# ARC_Shield_0_3.net
KiCad netlist of a schematic drawn in EAGLE
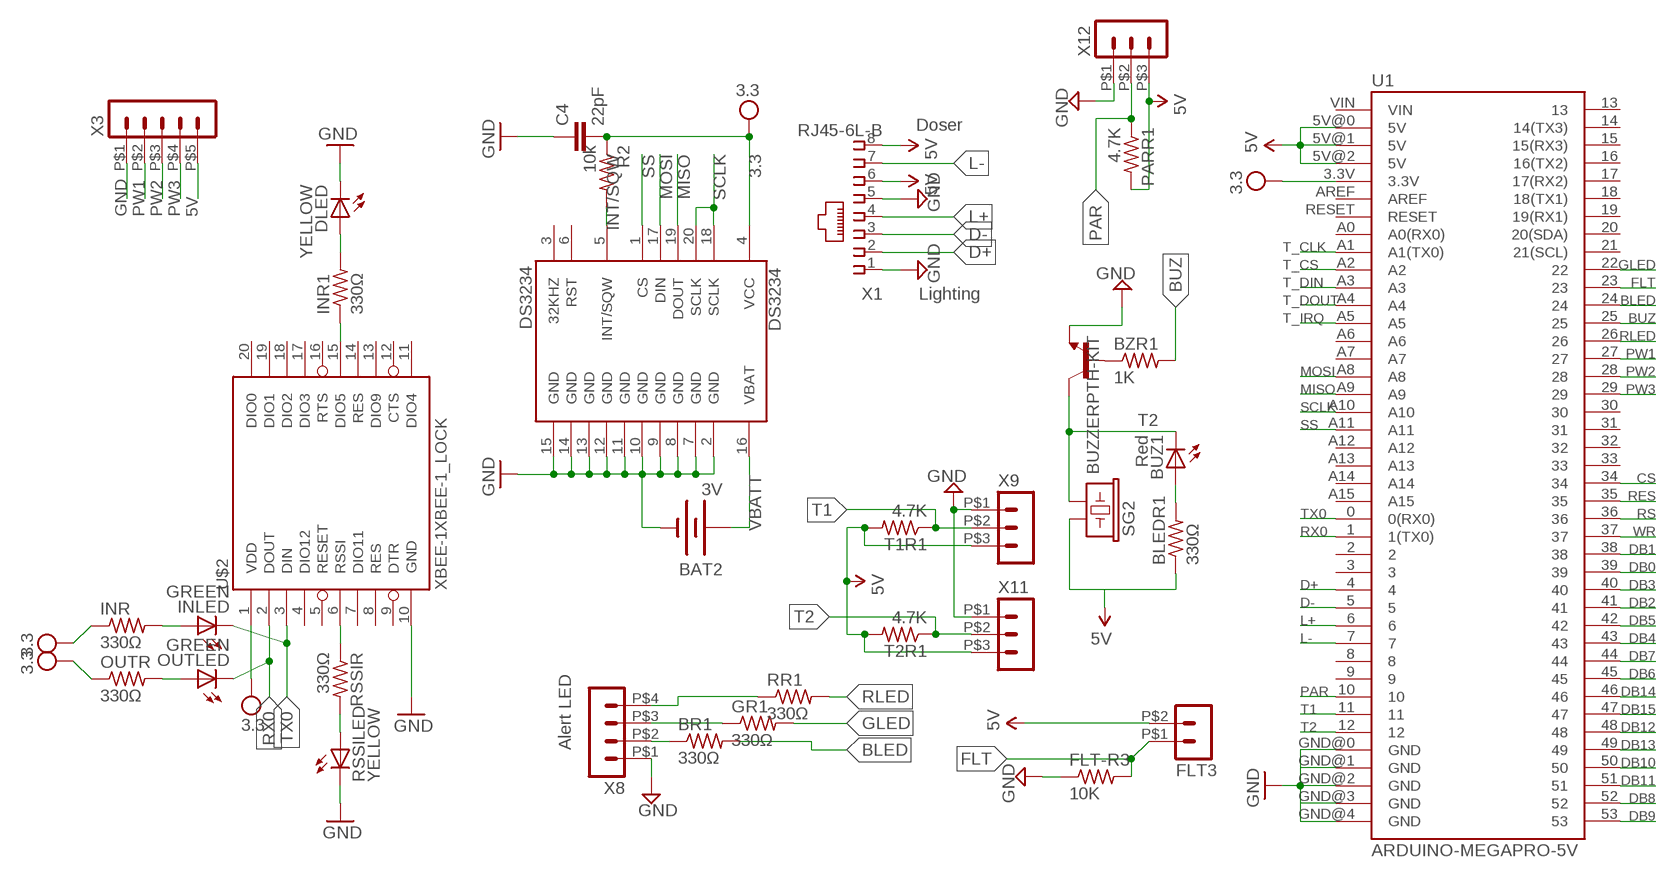
[diagram p0: schematic, sheet 1]

(export (version "E")
  (design (tool "Eeschema 10.0.6"))
  (components
    (comp (ref "BAT2")
      (value "3V")
      (footprint "eagle-import:BATTCON_12MM_CURVED")
      (libsource (lib "eagle-import") (part "BATTERY"))
    )
    (comp (ref "BLEDR1")
      (value "330Ω")
      (footprint "eagle-import:0204_7")
      (libsource (lib "eagle-import") (part "R-US_0204/7"))
    )
    (comp (ref "BR1")
      (value "330Ω")
      (footprint "eagle-import:0204_7")
      (libsource (lib "eagle-import") (part "R-US_0204/7"))
    )
    (comp (ref "BUZ1")
      (value "Red")
      (footprint "eagle-import:LED3MM")
      (libsource (lib "eagle-import") (part "LED3MM"))
    )
    (comp (ref "BZR1")
      (value "1K")
      (footprint "eagle-import:0204_7")
      (libsource (lib "eagle-import") (part "R-US_0204/7"))
    )
    (comp (ref "C4")
      (value "22pF")
      (footprint "eagle-import:C5B3")
      (libsource (lib "eagle-import") (part "C5/3"))
    )
    (comp (ref "DLED")
      (value "YELLOW")
      (footprint "eagle-import:LED3MM")
      (libsource (lib "eagle-import") (part "LED3MM"))
    )
    (comp (ref "DS3234")
      (value "DS3234")
      (footprint "eagle-import:DS3234")
      (libsource (lib "eagle-import") (part "DS3234"))
    )
    (comp (ref "FLT-R3")
      (value "10K")
      (footprint "eagle-import:0204_7")
      (libsource (lib "eagle-import") (part "R-US_0204/7"))
    )
    (comp (ref "FLT3")
      (value "HEADER_POS2_43045-0200")
      (footprint "eagle-import:43045-0200")
      (libsource (lib "eagle-import") (part "HEADER_POS2_?43045-0200"))
    )
    (comp (ref "GR1")
      (value "330Ω")
      (footprint "eagle-import:0204_7")
      (libsource (lib "eagle-import") (part "R-US_0204/7"))
    )
    (comp (ref "INLED")
      (value "GREEN")
      (footprint "eagle-import:LED3MM")
      (libsource (lib "eagle-import") (part "LED3MM"))
    )
    (comp (ref "INR")
      (value "330Ω")
      (footprint "eagle-import:0204_7")
      (libsource (lib "eagle-import") (part "R-US_0204/7"))
    )
    (comp (ref "INR1")
      (value "330Ω")
      (footprint "eagle-import:0204_7")
      (libsource (lib "eagle-import") (part "R-US_0204/7"))
    )
    (comp (ref "OUTLED")
      (value "GREEN")
      (footprint "eagle-import:LED3MM")
      (libsource (lib "eagle-import") (part "LED3MM"))
    )
    (comp (ref "OUTR")
      (value "330Ω")
      (footprint "eagle-import:0204_7")
      (libsource (lib "eagle-import") (part "R-US_0204/7"))
    )
    (comp (ref "PARR1")
      (value "4.7K")
      (footprint "eagle-import:0204_7")
      (libsource (lib "eagle-import") (part "R-US_0204/7"))
    )
    (comp (ref "R2")
      (value "10k")
      (footprint "eagle-import:0204_7")
      (libsource (lib "eagle-import") (part "R-US_0204/7"))
    )
    (comp (ref "RR1")
      (value "330Ω")
      (footprint "eagle-import:0204_7")
      (libsource (lib "eagle-import") (part "R-US_0204/7"))
    )
    (comp (ref "RSSILED")
      (value "YELLOW")
      (footprint "eagle-import:LED3MM")
      (libsource (lib "eagle-import") (part "LED3MM"))
    )
    (comp (ref "RSSIR")
      (value "330Ω")
      (footprint "eagle-import:0204_7")
      (libsource (lib "eagle-import") (part "R-US_0204/7"))
    )
    (comp (ref "SG2")
      (value "BUZZERPTH-KIT")
      (footprint "eagle-import:BUZZER-12MM-KIT")
      (libsource (lib "eagle-import") (part "BUZZERPTH-KIT"))
    )
    (comp (ref "T1R1")
      (value "4.7K")
      (footprint "eagle-import:0204_7")
      (libsource (lib "eagle-import") (part "R-US_0204/7"))
    )
    (comp (ref "T2")
      (value "-NPN-TO92")
      (footprint "eagle-import:TO92")
      (libsource (lib "eagle-import") (part "-NPN-TO92"))
    )
    (comp (ref "T2R1")
      (value "4.7K")
      (footprint "eagle-import:0204_7")
      (libsource (lib "eagle-import") (part "R-US_0204/7"))
    )
    (comp (ref "U$2")
      (value "XBEE-1XBEE-1_LOCK")
      (footprint "eagle-import:XBEE-1_LOCK")
      (libsource (lib "eagle-import") (part "XBEE-1XBEE-1_LOCK"))
    )
    (comp (ref "U1")
      (value "ARDUINO-MEGAPRO-5V")
      (footprint "eagle-import:ARDUINO_MEGA-PRO-5V")
      (libsource (lib "eagle-import") (part "ARDUINO-MEGAPRO-5V"))
    )
    (comp (ref "X1")
      (value "RJ45-6L-B")
      (footprint "eagle-import:RJ45-NO-SHIELD")
      (libsource (lib "eagle-import") (part "RJ45-6L-B"))
    )
    (comp (ref "X3")
      (value "HEADER_POS5_43650-0500")
      (footprint "eagle-import:43650-0500")
      (libsource (lib "eagle-import") (part "HEADER_POS5_?43650-0500"))
    )
    (comp (ref "X8")
      (value "HEADER_POS4_43045-0401")
      (footprint "eagle-import:43045-0400")
      (libsource (lib "eagle-import") (part "HEADER_POS4_?43045-0401"))
    )
    (comp (ref "X9")
      (value "HEADER_POS3_43650-0300")
      (footprint "eagle-import:43650-0300")
      (libsource (lib "eagle-import") (part "HEADER_POS3_?43650-0300"))
    )
    (comp (ref "X11")
      (value "HEADER_POS3_43650-0300")
      (footprint "eagle-import:43650-0300")
      (libsource (lib "eagle-import") (part "HEADER_POS3_?43650-0300"))
    )
    (comp (ref "X12")
      (value "HEADER_POS3_43650-0300")
      (footprint "eagle-import:43650-0300")
      (libsource (lib "eagle-import") (part "HEADER_POS3_?43650-0300"))
    )
  )
  (nets
    (net (code "1") (name "/CS") (class "Default")
      (node (ref "U1") (pin "34") (pinfunction "34_34") (pintype "bidirectional"))
    )
    (net (code "2") (name "/DB0") (class "Default")
      (node (ref "U1") (pin "39") (pinfunction "39_39") (pintype "bidirectional"))
    )
    (net (code "3") (name "/DB1") (class "Default")
      (node (ref "U1") (pin "38") (pinfunction "38_38") (pintype "bidirectional"))
    )
    (net (code "4") (name "/DB2") (class "Default")
      (node (ref "U1") (pin "41") (pinfunction "41_41") (pintype "bidirectional"))
    )
    (net (code "5") (name "/DB3") (class "Default")
      (node (ref "U1") (pin "40") (pinfunction "40_40") (pintype "bidirectional"))
    )
    (net (code "6") (name "/DB4") (class "Default")
      (node (ref "U1") (pin "43") (pinfunction "43_43") (pintype "bidirectional"))
    )
    (net (code "7") (name "/DB5") (class "Default")
      (node (ref "U1") (pin "42") (pinfunction "42_42") (pintype "bidirectional"))
    )
    (net (code "8") (name "/DB6") (class "Default")
      (node (ref "U1") (pin "45") (pinfunction "45_45") (pintype "bidirectional"))
    )
    (net (code "9") (name "/DB7") (class "Default")
      (node (ref "U1") (pin "44") (pinfunction "44_44") (pintype "bidirectional"))
    )
    (net (code "10") (name "/DB8") (class "Default")
      (node (ref "U1") (pin "52") (pinfunction "52_52") (pintype "bidirectional"))
    )
    (net (code "11") (name "/DB9") (class "Default")
      (node (ref "U1") (pin "53") (pinfunction "53_53") (pintype "bidirectional"))
    )
    (net (code "12") (name "/DB10") (class "Default")
      (node (ref "U1") (pin "50") (pinfunction "50_50") (pintype "bidirectional"))
    )
    (net (code "13") (name "/DB11") (class "Default")
      (node (ref "U1") (pin "51") (pinfunction "51_51") (pintype "bidirectional"))
    )
    (net (code "14") (name "/DB12") (class "Default")
      (node (ref "U1") (pin "48") (pinfunction "48_48") (pintype "bidirectional"))
    )
    (net (code "15") (name "/DB13") (class "Default")
      (node (ref "U1") (pin "49") (pinfunction "49_49") (pintype "bidirectional"))
    )
    (net (code "16") (name "/DB14") (class "Default")
      (node (ref "U1") (pin "46") (pinfunction "46_46") (pintype "bidirectional"))
    )
    (net (code "17") (name "/DB15") (class "Default")
      (node (ref "U1") (pin "47") (pinfunction "47_47") (pintype "bidirectional"))
    )
    (net (code "18") (name "/INT{slash}SQW") (class "Default")
      (node (ref "DS3234") (pin "5") (pinfunction "INT/SQW_5") (pintype "bidirectional"))
      (node (ref "R2") (pin "2") (pinfunction "2_2") (pintype "passive"))
    )
    (net (code "19") (name "/MISO") (class "Default")
      (node (ref "DS3234") (pin "19") (pinfunction "DOUT_19") (pintype "bidirectional"))
      (node (ref "U1") (pin "A9") (pinfunction "A9_A9") (pintype "bidirectional"))
    )
    (net (code "20") (name "/MOSI") (class "Default")
      (node (ref "DS3234") (pin "17") (pinfunction "DIN_17") (pintype "bidirectional"))
      (node (ref "U1") (pin "A8") (pinfunction "A8_A8") (pintype "bidirectional"))
    )
    (net (code "21") (name "/PW1") (class "Default")
      (node (ref "U1") (pin "27") (pinfunction "27_27") (pintype "bidirectional"))
      (node (ref "X3") (pin "P$2") (pinfunction "2_P$2") (pintype "passive"))
    )
    (net (code "22") (name "/PW2") (class "Default")
      (node (ref "U1") (pin "28") (pinfunction "28_28") (pintype "bidirectional"))
      (node (ref "X3") (pin "P$3") (pinfunction "3_P$3") (pintype "passive"))
    )
    (net (code "23") (name "/PW3") (class "Default")
      (node (ref "U1") (pin "29") (pinfunction "29_29") (pintype "bidirectional"))
      (node (ref "X3") (pin "P$4") (pinfunction "4_P$4") (pintype "passive"))
    )
    (net (code "24") (name "/RES") (class "Default")
      (node (ref "U1") (pin "35") (pinfunction "35_35") (pintype "bidirectional"))
    )
    (net (code "25") (name "/RS") (class "Default")
      (node (ref "U1") (pin "36") (pinfunction "36_36") (pintype "bidirectional"))
    )
    (net (code "26") (name "/SCLK") (class "Default")
      (node (ref "DS3234") (pin "18") (pinfunction "SCLK_18") (pintype "bidirectional"))
      (node (ref "DS3234") (pin "20") (pinfunction "SCLK_20") (pintype "bidirectional"))
      (node (ref "U1") (pin "A10") (pinfunction "A10_A10") (pintype "bidirectional"))
    )
    (net (code "27") (name "/SS") (class "Default")
      (node (ref "DS3234") (pin "1") (pinfunction "CS_1") (pintype "bidirectional"))
      (node (ref "U1") (pin "A11") (pinfunction "A11_A11") (pintype "bidirectional"))
    )
    (net (code "28") (name "/T_CLK") (class "Default")
      (node (ref "U1") (pin "A1") (pinfunction "A1(TX0)_A1") (pintype "bidirectional"))
    )
    (net (code "29") (name "/T_CS") (class "Default")
      (node (ref "U1") (pin "A2") (pinfunction "A2_A2") (pintype "bidirectional"))
    )
    (net (code "30") (name "/T_DIN") (class "Default")
      (node (ref "U1") (pin "A3") (pinfunction "A3_A3") (pintype "bidirectional"))
    )
    (net (code "31") (name "/T_DOUT") (class "Default")
      (node (ref "U1") (pin "A4") (pinfunction "A4_A4") (pintype "bidirectional"))
    )
    (net (code "32") (name "/T_IRQ") (class "Default")
      (node (ref "U1") (pin "A5") (pinfunction "A5_A5") (pintype "bidirectional"))
    )
    (net (code "33") (name "/VBATT") (class "Default")
      (node (ref "BAT2") (pin "PWR@1") (pinfunction "+_PWR@1") (pintype "power_in"))
      (node (ref "DS3234") (pin "16") (pinfunction "VBAT_16") (pintype "bidirectional"))
    )
    (net (code "34") (name "/WR") (class "Default")
      (node (ref "U1") (pin "37") (pinfunction "37_37") (pintype "bidirectional"))
    )
    (net (code "35") (name "3.3") (class "Default")
      (node (ref "C4") (pin "2") (pinfunction "2_2") (pintype "passive"))
      (node (ref "DS3234") (pin "4") (pinfunction "VCC_4") (pintype "bidirectional"))
      (node (ref "INR") (pin "1") (pinfunction "1_1") (pintype "passive"))
      (node (ref "OUTR") (pin "1") (pinfunction "1_1") (pintype "passive"))
      (node (ref "R2") (pin "1") (pinfunction "1_1") (pintype "passive"))
      (node (ref "U$2") (pin "1") (pinfunction "VDD_1") (pintype "power_in"))
      (node (ref "U1") (pin "3.3V") (pinfunction "3.3V_3.3V") (pintype "bidirectional"))
    )
    (net (code "36") (name "5V") (class "Default")
      (node (ref "BLEDR1") (pin "1") (pinfunction "1_1") (pintype "passive"))
      (node (ref "FLT3") (pin "P$2") (pinfunction "2_P$2") (pintype "passive"))
      (node (ref "PARR1") (pin "2") (pinfunction "2_2") (pintype "passive"))
      (node (ref "SG2") (pin "+") (pinfunction "1_+") (pintype "passive"))
      (node (ref "T1R1") (pin "2") (pinfunction "2_2") (pintype "passive"))
      (node (ref "T2R1") (pin "2") (pinfunction "2_2") (pintype "passive"))
      (node (ref "U1") (pin "5V@0") (pinfunction "5V_5V@0") (pintype "bidirectional"))
      (node (ref "U1") (pin "5V@1") (pinfunction "5V_5V@1") (pintype "bidirectional"))
      (node (ref "U1") (pin "5V@2") (pinfunction "5V_5V@2") (pintype "bidirectional"))
      (node (ref "X1") (pin "6") (pinfunction "6_6") (pintype "passive"))
      (node (ref "X1") (pin "8") (pinfunction "8_8") (pintype "passive"))
      (node (ref "X11") (pin "P$3") (pinfunction "3_P$3") (pintype "passive"))
      (node (ref "X12") (pin "P$3") (pinfunction "3_P$3") (pintype "passive"))
      (node (ref "X3") (pin "P$5") (pinfunction "5_P$5") (pintype "passive"))
      (node (ref "X9") (pin "P$3") (pinfunction "3_P$3") (pintype "passive"))
    )
    (net (code "37") (name "BLED") (class "Default")
      (node (ref "BR1") (pin "2") (pinfunction "2_2") (pintype "passive"))
      (node (ref "U1") (pin "24") (pinfunction "24_24") (pintype "bidirectional"))
    )
    (net (code "38") (name "BUZ") (class "Default")
      (node (ref "BZR1") (pin "2") (pinfunction "2_2") (pintype "passive"))
      (node (ref "U1") (pin "25") (pinfunction "25_25") (pintype "bidirectional"))
    )
    (net (code "39") (name "D+") (class "Default")
      (node (ref "U1") (pin "4") (pinfunction "4_4") (pintype "bidirectional"))
      (node (ref "X1") (pin "2") (pinfunction "2_2") (pintype "passive"))
    )
    (net (code "40") (name "D-") (class "Default")
      (node (ref "U1") (pin "5") (pinfunction "5_5") (pintype "bidirectional"))
      (node (ref "X1") (pin "3") (pinfunction "3_3") (pintype "passive"))
    )
    (net (code "41") (name "FLT") (class "Default")
      (node (ref "FLT-R3") (pin "2") (pinfunction "2_2") (pintype "passive"))
      (node (ref "FLT3") (pin "P$1") (pinfunction "1_P$1") (pintype "passive"))
      (node (ref "U1") (pin "23") (pinfunction "23_23") (pintype "bidirectional"))
    )
    (net (code "42") (name "GLED") (class "Default")
      (node (ref "GR1") (pin "2") (pinfunction "2_2") (pintype "passive"))
      (node (ref "U1") (pin "22") (pinfunction "22_22") (pintype "bidirectional"))
    )
    (net (code "43") (name "GND") (class "Default")
      (node (ref "BAT2") (pin "GND") (pinfunction "-_GND") (pintype "power_in"))
      (node (ref "C4") (pin "1") (pinfunction "1_1") (pintype "passive"))
      (node (ref "DLED") (pin "K") (pinfunction "C_K") (pintype "passive"))
      (node (ref "DS3234") (pin "10") (pinfunction "GND_10") (pintype "bidirectional"))
      (node (ref "DS3234") (pin "11") (pinfunction "GND_11") (pintype "bidirectional"))
      (node (ref "DS3234") (pin "12") (pinfunction "GND_12") (pintype "bidirectional"))
      (node (ref "DS3234") (pin "13") (pinfunction "GND_13") (pintype "bidirectional"))
      (node (ref "DS3234") (pin "14") (pinfunction "GND_14") (pintype "bidirectional"))
      (node (ref "DS3234") (pin "15") (pinfunction "GND_15") (pintype "bidirectional"))
      (node (ref "DS3234") (pin "2") (pinfunction "GND_2") (pintype "bidirectional"))
      (node (ref "DS3234") (pin "7") (pinfunction "GND_7") (pintype "bidirectional"))
      (node (ref "DS3234") (pin "8") (pinfunction "GND_8") (pintype "bidirectional"))
      (node (ref "DS3234") (pin "9") (pinfunction "GND_9") (pintype "bidirectional"))
      (node (ref "FLT-R3") (pin "1") (pinfunction "1_1") (pintype "passive"))
      (node (ref "RSSILED") (pin "K") (pinfunction "C_K") (pintype "passive"))
      (node (ref "T2") (pin "1") (pinfunction "E_1") (pintype "passive"))
      (node (ref "U$2") (pin "10") (pinfunction "GND_10") (pintype "power_in"))
      (node (ref "U1") (pin "GND@0") (pinfunction "GND_GND@0") (pintype "bidirectional"))
      (node (ref "U1") (pin "GND@1") (pinfunction "GND_GND@1") (pintype "bidirectional"))
      (node (ref "U1") (pin "GND@2") (pinfunction "GND_GND@2") (pintype "bidirectional"))
      (node (ref "U1") (pin "GND@3") (pinfunction "GND_GND@3") (pintype "bidirectional"))
      (node (ref "U1") (pin "GND@4") (pinfunction "GND_GND@4") (pintype "bidirectional"))
      (node (ref "X1") (pin "1") (pinfunction "1_1") (pintype "passive"))
      (node (ref "X1") (pin "5") (pinfunction "5_5") (pintype "passive"))
      (node (ref "X11") (pin "P$1") (pinfunction "1_P$1") (pintype "passive"))
      (node (ref "X12") (pin "P$1") (pinfunction "1_P$1") (pintype "passive"))
      (node (ref "X3") (pin "P$1") (pinfunction "1_P$1") (pintype "passive"))
      (node (ref "X8") (pin "P$1") (pinfunction "1_P$1") (pintype "passive"))
      (node (ref "X9") (pin "P$1") (pinfunction "1_P$1") (pintype "passive"))
    )
    (net (code "44") (name "L+") (class "Default")
      (node (ref "U1") (pin "6") (pinfunction "6_6") (pintype "bidirectional"))
      (node (ref "X1") (pin "4") (pinfunction "4_4") (pintype "passive"))
    )
    (net (code "45") (name "L-") (class "Default")
      (node (ref "U1") (pin "7") (pinfunction "7_7") (pintype "bidirectional"))
      (node (ref "X1") (pin "7") (pinfunction "7_7") (pintype "passive"))
    )
    (net (code "46") (name "Net-(BLEDR1-Pad2)") (class "Default")
      (node (ref "BLEDR1") (pin "2") (pinfunction "2_2") (pintype "passive"))
      (node (ref "BUZ1") (pin "A") (pinfunction "A_A") (pintype "passive"))
    )
    (net (code "47") (name "Net-(BUZ1-C)") (class "Default")
      (node (ref "BUZ1") (pin "K") (pinfunction "C_K") (pintype "passive"))
      (node (ref "SG2") (pin "-") (pinfunction "2_-") (pintype "passive"))
      (node (ref "T2") (pin "3") (pinfunction "C_3") (pintype "passive"))
    )
    (net (code "48") (name "Net-(DLED-PadA)") (class "Default")
      (node (ref "DLED") (pin "A") (pinfunction "A_A") (pintype "passive"))
      (node (ref "INR1") (pin "2") (pinfunction "2_2") (pintype "passive"))
    )
    (net (code "49") (name "Net-(INLED-PadA)") (class "Default")
      (node (ref "INLED") (pin "A") (pinfunction "A_A") (pintype "passive"))
      (node (ref "INR") (pin "2") (pinfunction "2_2") (pintype "passive"))
    )
    (net (code "50") (name "Net-(OUTLED-PadA)") (class "Default")
      (node (ref "OUTLED") (pin "A") (pinfunction "A_A") (pintype "passive"))
      (node (ref "OUTR") (pin "2") (pinfunction "2_2") (pintype "passive"))
    )
    (net (code "51") (name "Net-(RSSILED-PadA)") (class "Default")
      (node (ref "RSSILED") (pin "A") (pinfunction "A_A") (pintype "passive"))
      (node (ref "RSSIR") (pin "2") (pinfunction "2_2") (pintype "passive"))
    )
    (net (code "52") (name "Net-(T2-B)") (class "Default")
      (node (ref "BZR1") (pin "1") (pinfunction "1_1") (pintype "passive"))
      (node (ref "T2") (pin "2") (pinfunction "B_2") (pintype "passive"))
    )
    (net (code "53") (name "Net-(U$2-DIO5)") (class "Default")
      (node (ref "INR1") (pin "1") (pinfunction "1_1") (pintype "passive"))
      (node (ref "U$2") (pin "15") (pinfunction "DIO5_15") (pintype "bidirectional"))
    )
    (net (code "54") (name "Net-(U$2-RSSI)") (class "Default")
      (node (ref "RSSIR") (pin "1") (pinfunction "1_1") (pintype "passive"))
      (node (ref "U$2") (pin "6") (pinfunction "RSSI_6") (pintype "bidirectional"))
    )
    (net (code "55") (name "Net-(X8-2)") (class "Default")
      (node (ref "BR1") (pin "1") (pinfunction "1_1") (pintype "passive"))
      (node (ref "X8") (pin "P$2") (pinfunction "2_P$2") (pintype "passive"))
    )
    (net (code "56") (name "Net-(X8-3)") (class "Default")
      (node (ref "GR1") (pin "1") (pinfunction "1_1") (pintype "passive"))
      (node (ref "X8") (pin "P$3") (pinfunction "3_P$3") (pintype "passive"))
    )
    (net (code "57") (name "Net-(X8-4)") (class "Default")
      (node (ref "RR1") (pin "1") (pinfunction "1_1") (pintype "passive"))
      (node (ref "X8") (pin "P$4") (pinfunction "4_P$4") (pintype "passive"))
    )
    (net (code "58") (name "PAR") (class "Default")
      (node (ref "PARR1") (pin "1") (pinfunction "1_1") (pintype "passive"))
      (node (ref "U1") (pin "10") (pinfunction "10_10") (pintype "bidirectional"))
      (node (ref "X12") (pin "P$2") (pinfunction "2_P$2") (pintype "passive"))
    )
    (net (code "59") (name "RLED") (class "Default")
      (node (ref "RR1") (pin "2") (pinfunction "2_2") (pintype "passive"))
      (node (ref "U1") (pin "26") (pinfunction "26_26") (pintype "bidirectional"))
    )
    (net (code "60") (name "RX0") (class "Default")
      (node (ref "OUTLED") (pin "K") (pinfunction "C_K") (pintype "passive"))
      (node (ref "U$2") (pin "2") (pinfunction "DOUT_2") (pintype "output"))
      (node (ref "U1") (pin "1") (pinfunction "1(TX0)_1") (pintype "bidirectional"))
    )
    (net (code "61") (name "T1") (class "Default")
      (node (ref "T1R1") (pin "1") (pinfunction "1_1") (pintype "passive"))
      (node (ref "U1") (pin "11") (pinfunction "11_11") (pintype "bidirectional"))
      (node (ref "X9") (pin "P$2") (pinfunction "2_P$2") (pintype "passive"))
    )
    (net (code "62") (name "T2") (class "Default")
      (node (ref "T2R1") (pin "1") (pinfunction "1_1") (pintype "passive"))
      (node (ref "U1") (pin "12") (pinfunction "12_12") (pintype "bidirectional"))
      (node (ref "X11") (pin "P$2") (pinfunction "2_P$2") (pintype "passive"))
    )
    (net (code "63") (name "TX0") (class "Default")
      (node (ref "INLED") (pin "K") (pinfunction "C_K") (pintype "passive"))
      (node (ref "U$2") (pin "3") (pinfunction "DIN_3") (pintype "input"))
      (node (ref "U1") (pin "0") (pinfunction "0(RX0)_0") (pintype "bidirectional"))
    )
    (net (code "64") (name "unconnected-(DS3234-32KHZ-Pad3)") (class "Default")
      (node (ref "DS3234") (pin "3") (pinfunction "32KHZ_3") (pintype "bidirectional"))
    )
    (net (code "65") (name "unconnected-(DS3234-RST-Pad6)") (class "Default")
      (node (ref "DS3234") (pin "6") (pinfunction "RST_6") (pintype "bidirectional"))
    )
    (net (code "66") (name "unconnected-(U$2-CTS-Pad12)") (class "Default")
      (node (ref "U$2") (pin "12") (pinfunction "CTS_12") (pintype "output"))
    )
    (net (code "67") (name "unconnected-(U$2-DIO0-Pad20)") (class "Default")
      (node (ref "U$2") (pin "20") (pinfunction "DIO0_20") (pintype "bidirectional"))
    )
    (net (code "68") (name "unconnected-(U$2-DIO1-Pad19)") (class "Default")
      (node (ref "U$2") (pin "19") (pinfunction "DIO1_19") (pintype "bidirectional"))
    )
    (net (code "69") (name "unconnected-(U$2-DIO2-Pad18)") (class "Default")
      (node (ref "U$2") (pin "18") (pinfunction "DIO2_18") (pintype "bidirectional"))
    )
    (net (code "70") (name "unconnected-(U$2-DIO3-Pad17)") (class "Default")
      (node (ref "U$2") (pin "17") (pinfunction "DIO3_17") (pintype "bidirectional"))
    )
    (net (code "71") (name "unconnected-(U$2-DIO4-Pad11)") (class "Default")
      (node (ref "U$2") (pin "11") (pinfunction "DIO4_11") (pintype "bidirectional"))
    )
    (net (code "72") (name "unconnected-(U$2-DIO9-Pad13)") (class "Default")
      (node (ref "U$2") (pin "13") (pinfunction "DIO9_13") (pintype "bidirectional"))
    )
    (net (code "73") (name "unconnected-(U$2-DIO11-Pad7)") (class "Default")
      (node (ref "U$2") (pin "7") (pinfunction "DIO11_7") (pintype "bidirectional"))
    )
    (net (code "74") (name "unconnected-(U$2-DIO12-Pad4)") (class "Default")
      (node (ref "U$2") (pin "4") (pinfunction "DIO12_4") (pintype "bidirectional"))
    )
    (net (code "75") (name "unconnected-(U$2-DTR-Pad9)") (class "Default")
      (node (ref "U$2") (pin "9") (pinfunction "DTR_9") (pintype "bidirectional"))
    )
    (net (code "76") (name "unconnected-(U$2-RES-Pad8)") (class "Default")
      (node (ref "U$2") (pin "8") (pinfunction "RES_8") (pintype "bidirectional"))
    )
    (net (code "77") (name "unconnected-(U$2-RES-Pad14)") (class "Default")
      (node (ref "U$2") (pin "14") (pinfunction "RES_14") (pintype "bidirectional"))
    )
    (net (code "78") (name "unconnected-(U$2-RESET-Pad5)") (class "Default")
      (node (ref "U$2") (pin "5") (pinfunction "RESET_5") (pintype "input"))
    )
    (net (code "79") (name "unconnected-(U$2-RTS-Pad16)") (class "Default")
      (node (ref "U$2") (pin "16") (pinfunction "RTS_16") (pintype "input"))
    )
    (net (code "80") (name "unconnected-(U1-14(TX3)-Pad14)") (class "Default")
      (node (ref "U1") (pin "14") (pinfunction "14(TX3)_14") (pintype "bidirectional"))
    )
    (net (code "81") (name "unconnected-(U1-15(RX3)-Pad15)") (class "Default")
      (node (ref "U1") (pin "15") (pinfunction "15(RX3)_15") (pintype "bidirectional"))
    )
    (net (code "82") (name "unconnected-(U1-16(TX2)-Pad16)") (class "Default")
      (node (ref "U1") (pin "16") (pinfunction "16(TX2)_16") (pintype "bidirectional"))
    )
    (net (code "83") (name "unconnected-(U1-17(RX2)-Pad17)") (class "Default")
      (node (ref "U1") (pin "17") (pinfunction "17(RX2)_17") (pintype "bidirectional"))
    )
    (net (code "84") (name "unconnected-(U1-18(TX1)-Pad18)") (class "Default")
      (node (ref "U1") (pin "18") (pinfunction "18(TX1)_18") (pintype "bidirectional"))
    )
    (net (code "85") (name "unconnected-(U1-19(RX1)-Pad19)") (class "Default")
      (node (ref "U1") (pin "19") (pinfunction "19(RX1)_19") (pintype "bidirectional"))
    )
    (net (code "86") (name "unconnected-(U1-20(SDA)-Pad20)") (class "Default")
      (node (ref "U1") (pin "20") (pinfunction "20(SDA)_20") (pintype "bidirectional"))
    )
    (net (code "87") (name "unconnected-(U1-21(SCL)-Pad21)") (class "Default")
      (node (ref "U1") (pin "21") (pinfunction "21(SCL)_21") (pintype "bidirectional"))
    )
    (net (code "88") (name "unconnected-(U1-A0(RX0)-PadA0)") (class "Default")
      (node (ref "U1") (pin "A0") (pinfunction "A0(RX0)_A0") (pintype "bidirectional"))
    )
    (net (code "89") (name "unconnected-(U1-Pad2)") (class "Default")
      (node (ref "U1") (pin "2") (pinfunction "2_2") (pintype "bidirectional"))
    )
    (net (code "90") (name "unconnected-(U1-Pad3)") (class "Default")
      (node (ref "U1") (pin "3") (pinfunction "3_3") (pintype "bidirectional"))
    )
    (net (code "91") (name "unconnected-(U1-Pad8)") (class "Default")
      (node (ref "U1") (pin "8") (pinfunction "8_8") (pintype "bidirectional"))
    )
    (net (code "92") (name "unconnected-(U1-Pad9)") (class "Default")
      (node (ref "U1") (pin "9") (pinfunction "9_9") (pintype "bidirectional"))
    )
    (net (code "93") (name "unconnected-(U1-Pad13)") (class "Default")
      (node (ref "U1") (pin "13") (pinfunction "13_13") (pintype "bidirectional"))
    )
    (net (code "94") (name "unconnected-(U1-Pad30)") (class "Default")
      (node (ref "U1") (pin "30") (pinfunction "30_30") (pintype "bidirectional"))
    )
    (net (code "95") (name "unconnected-(U1-Pad31)") (class "Default")
      (node (ref "U1") (pin "31") (pinfunction "31_31") (pintype "bidirectional"))
    )
    (net (code "96") (name "unconnected-(U1-Pad32)") (class "Default")
      (node (ref "U1") (pin "32") (pinfunction "32_32") (pintype "bidirectional"))
    )
    (net (code "97") (name "unconnected-(U1-Pad33)") (class "Default")
      (node (ref "U1") (pin "33") (pinfunction "33_33") (pintype "bidirectional"))
    )
    (net (code "98") (name "unconnected-(U1-PadA6)") (class "Default")
      (node (ref "U1") (pin "A6") (pinfunction "A6_A6") (pintype "bidirectional"))
    )
    (net (code "99") (name "unconnected-(U1-PadA7)") (class "Default")
      (node (ref "U1") (pin "A7") (pinfunction "A7_A7") (pintype "bidirectional"))
    )
    (net (code "100") (name "unconnected-(U1-PadA12)") (class "Default")
      (node (ref "U1") (pin "A12") (pinfunction "A12_A12") (pintype "bidirectional"))
    )
    (net (code "101") (name "unconnected-(U1-PadA13)") (class "Default")
      (node (ref "U1") (pin "A13") (pinfunction "A13_A13") (pintype "bidirectional"))
    )
    (net (code "102") (name "unconnected-(U1-PadA14)") (class "Default")
      (node (ref "U1") (pin "A14") (pinfunction "A14_A14") (pintype "bidirectional"))
    )
    (net (code "103") (name "unconnected-(U1-PadA15)") (class "Default")
      (node (ref "U1") (pin "A15") (pinfunction "A15_A15") (pintype "bidirectional"))
    )
    (net (code "104") (name "unconnected-(U1-PadAREF)") (class "Default")
      (node (ref "U1") (pin "AREF") (pinfunction "AREF_AREF") (pintype "bidirectional"))
    )
    (net (code "105") (name "unconnected-(U1-PadRESET)") (class "Default")
      (node (ref "U1") (pin "RESET") (pinfunction "RESET_RESET") (pintype "bidirectional"))
    )
    (net (code "106") (name "unconnected-(U1-PadVIN)") (class "Default")
      (node (ref "U1") (pin "VIN") (pinfunction "VIN_VIN") (pintype "bidirectional"))
    )
  )
)
